# SCH_esp-firework-firing-system-hw1.net
KiCad netlist of a schematic drawn in EasyEDA
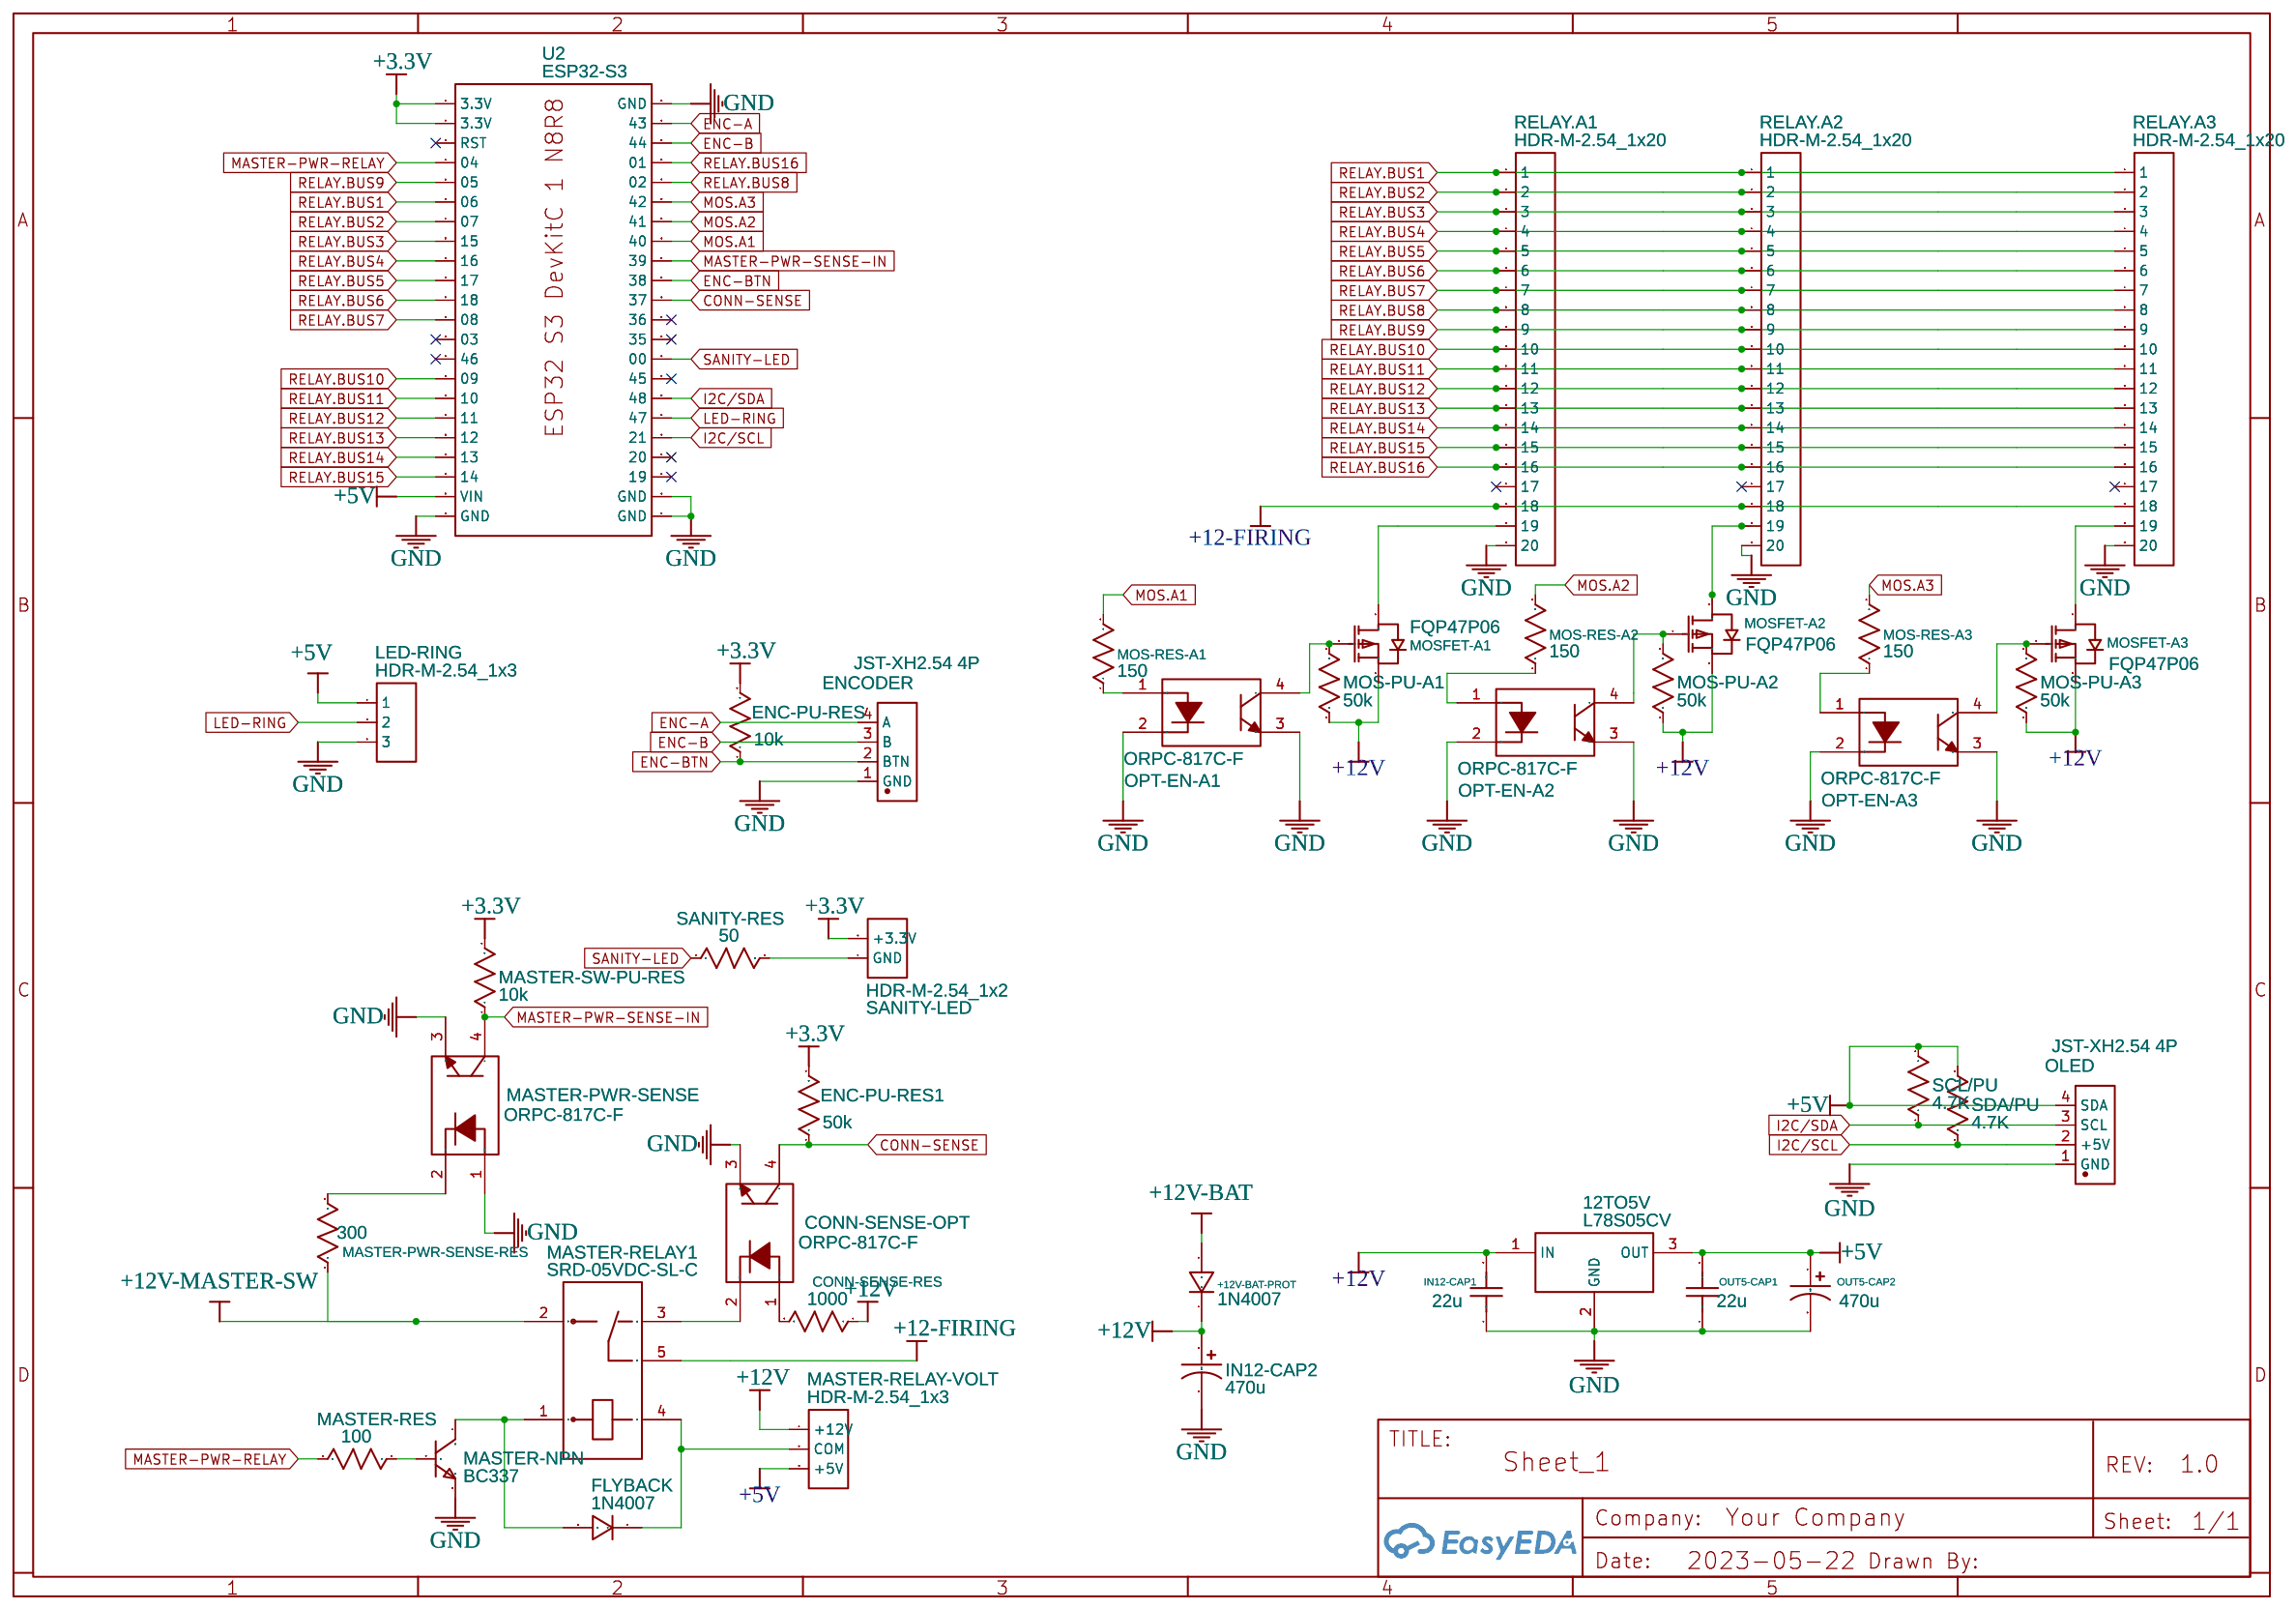
[diagram p0: schematic sheet]

(export (version "E")
  (design (tool "Eeschema 10.0.6"))
  (components
    (comp (ref "+12V-BAT-PROT")
      (value "1N4007")
      (fields (field (name "BOM_Supplier Part") "C106903"))
      (libsource (lib "") (part "1N4007"))
    )
    (comp (ref "12TO5V")
      (value "L78S05CV")
      (fields (field (name "BOM_Supplier Part") "C33043"))
      (libsource (lib "") (part "L78S05CV"))
    )
    (comp (ref "CONN-SENSE-OPT")
      (value "ORPC-817C-F")
      (fields (field (name "BOM_Supplier Part") "C2842770"))
      (libsource (lib "") (part "ORPC-817C-F_2"))
    )
    (comp (ref "CONN-SENSE-RES") (value "1000") (libsource (lib "") (part "R_AXIAL-0.3_US_6")))
    (comp (ref "ENC-PU-RES") (value "10k") (libsource (lib "") (part "R_AXIAL-0.3_US")))
    (comp (ref "ENC-PU-RES1") (value "50k") (libsource (lib "") (part "R_AXIAL-0.3_US")))
    (comp (ref "ENCODER") (value "JST-XH2.54 4P") (libsource (lib "") (part "JST-XH2.54 4P_1")))
    (comp (ref "FLYBACK")
      (value "1N4007")
      (fields (field (name "BOM_Supplier Part") "C106903"))
      (libsource (lib "") (part "1N4007_1"))
    )
    (comp (ref "IN12-CAP1") (value "22u") (libsource (lib "") (part "C_RAD-0.1_US")))
    (comp (ref "IN12-CAP2") (value "470u") (libsource (lib "") (part "CE_TH_D6.3×F2.5_US_1")))
    (comp (ref "LED-RING")
      (value "HDR-M-2.54_1x3")
      (fields (field (name "BOM_Supplier Part") "C180248"))
      (libsource (lib "") (part "HDR-M-2.54_1x3_1"))
    )
    (comp (ref "MASTER-NPN") (value "BC337") (libsource (lib "") (part "BC337")))
    (comp (ref "MASTER-PWR-SENSE")
      (value "ORPC-817C-F")
      (fields (field (name "BOM_Supplier Part") "C2842770"))
      (libsource (lib "") (part "ORPC-817C-F"))
    )
    (comp (ref "MASTER-PWR-SENSE-RES") (value "300") (libsource (lib "") (part "R_AXIAL-0.3_US_9")))
    (comp (ref "MASTER-RELAY-VOLT")
      (value "HDR-M-2.54_1x3")
      (fields (field (name "BOM_Supplier Part") "C180248"))
      (libsource (lib "") (part "HDR-M-2.54_1x3"))
    )
    (comp (ref "MASTER-RELAY1")
      (value "SRD-05VDC-SL-C")
      (fields (field (name "BOM_Supplier Part") "C35449"))
      (libsource (lib "") (part "SRD-05VDC-SL-C"))
    )
    (comp (ref "MASTER-RES") (value "100") (libsource (lib "") (part "R_AXIAL-0.3_US_4")))
    (comp (ref "MASTER-SW-PU-RES") (value "10k") (libsource (lib "") (part "R_AXIAL-0.3_US_8")))
    (comp (ref "MOS-PU-A1") (value "50k") (libsource (lib "") (part "R_AXIAL-0.3_US_3")))
    (comp (ref "MOS-PU-A2") (value "50k") (libsource (lib "") (part "R_AXIAL-0.3_US_3")))
    (comp (ref "MOS-PU-A3") (value "50k") (libsource (lib "") (part "R_AXIAL-0.3_US_3")))
    (comp (ref "MOS-RES-A1") (value "150") (libsource (lib "") (part "R_AXIAL-0.3_US_2")))
    (comp (ref "MOS-RES-A2") (value "150") (libsource (lib "") (part "R_AXIAL-0.3_US_2")))
    (comp (ref "MOS-RES-A3") (value "150") (libsource (lib "") (part "R_AXIAL-0.3_US_2")))
    (comp (ref "MOSFET-A1")
      (value "FQP47P06")
      (fields (field (name "BOM_Supplier Part") "C462765"))
      (libsource (lib "") (part "FQP47P06"))
    )
    (comp (ref "MOSFET-A2")
      (value "FQP47P06")
      (fields (field (name "BOM_Supplier Part") "C462765"))
      (libsource (lib "") (part "FQP47P06"))
    )
    (comp (ref "MOSFET-A3")
      (value "FQP47P06")
      (fields (field (name "BOM_Supplier Part") "C462765"))
      (libsource (lib "") (part "FQP47P06"))
    )
    (comp (ref "OLED") (value "JST-XH2.54 4P") (libsource (lib "") (part "JST-XH2.54 4P")))
    (comp (ref "OPT-EN-A1")
      (value "ORPC-817C-F")
      (fields (field (name "BOM_Supplier Part") "C2842770"))
      (libsource (lib "") (part "ORPC-817C-F_1"))
    )
    (comp (ref "OPT-EN-A2")
      (value "ORPC-817C-F")
      (fields (field (name "BOM_Supplier Part") "C2842770"))
      (libsource (lib "") (part "ORPC-817C-F_1"))
    )
    (comp (ref "OPT-EN-A3")
      (value "ORPC-817C-F")
      (fields (field (name "BOM_Supplier Part") "C2842770"))
      (libsource (lib "") (part "ORPC-817C-F_1"))
    )
    (comp (ref "OUT5-CAP1") (value "22u") (libsource (lib "") (part "C_RAD-0.1_US_1")))
    (comp (ref "OUT5-CAP2") (value "470u") (libsource (lib "") (part "CE_TH_D6.3×F2.5_US")))
    (comp (ref "RELAY.A1")
      (value "HDR-M-2.54_1x20")
      (fields (field (name "BOM_Supplier Part") "C50981"))
      (libsource (lib "") (part "HDR-M-2.54_1x20"))
    )
    (comp (ref "RELAY.A2")
      (value "HDR-M-2.54_1x20")
      (fields (field (name "BOM_Supplier Part") "C50981"))
      (libsource (lib "") (part "HDR-M-2.54_1x20"))
    )
    (comp (ref "RELAY.A3")
      (value "HDR-M-2.54_1x20")
      (fields (field (name "BOM_Supplier Part") "C50981"))
      (libsource (lib "") (part "HDR-M-2.54_1x20"))
    )
    (comp (ref "SANITY-LED")
      (value "HDR-M-2.54_1x2")
      (fields (field (name "BOM_Supplier Part") "C124375"))
      (libsource (lib "") (part "HDR-M-2.54_1x2"))
    )
    (comp (ref "SANITY-RES") (value "50") (libsource (lib "") (part "R_AXIAL-0.3_US_7")))
    (comp (ref "SCL/PU") (value "4.7K") (libsource (lib "") (part "R_AXIAL-0.3_US_1")))
    (comp (ref "SDA/PU") (value "4.7K") (libsource (lib "") (part "R_AXIAL-0.3_US_5")))
    (comp (ref "U2") (value "ESP32-S3") (libsource (lib "") (part "ESP32-S3")))
  )
  (nets
    (net (code "1") (name "+3.3V") (class "Default")
      (node (ref "ENC-PU-RES") (pin "2") (pinfunction "2_2") (pintype "unspecified"))
      (node (ref "ENC-PU-RES1") (pin "2") (pinfunction "2_2") (pintype "unspecified"))
      (node (ref "MASTER-SW-PU-RES") (pin "2") (pinfunction "2_2") (pintype "unspecified"))
      (node (ref "SANITY-LED") (pin "2") (pinfunction "+3.3V_2") (pintype "unspecified"))
      (node (ref "U2") (pin "1") (pinfunction "3.3V_1") (pintype "unspecified"))
      (node (ref "U2") (pin "2") (pinfunction "3.3V_2") (pintype "unspecified"))
    )
    (net (code "2") (name "+5V") (class "Default")
      (node (ref "12TO5V") (pin "3") (pinfunction "OUT_3") (pintype "passive"))
      (node (ref "LED-RING") (pin "1") (pinfunction "1_1") (pintype "input"))
      (node (ref "MASTER-RELAY-VOLT") (pin "3") (pinfunction "+5V_3") (pintype "input"))
      (node (ref "OLED") (pin "4") (pinfunction "SDA_4") (pintype "unspecified"))
      (node (ref "OUT5-CAP1") (pin "2") (pinfunction "2_2") (pintype "unspecified"))
      (node (ref "OUT5-CAP2") (pin "1") (pinfunction "1_1") (pintype "unspecified"))
      (node (ref "SCL/PU") (pin "2") (pinfunction "2_2") (pintype "unspecified"))
      (node (ref "SDA/PU") (pin "2") (pinfunction "2_2") (pintype "unspecified"))
      (node (ref "U2") (pin "21") (pinfunction "VIN_21") (pintype "unspecified"))
    )
    (net (code "3") (name "+12-FIRING") (class "Default")
      (node (ref "MASTER-RELAY1") (pin "5") (pinfunction "5_5") (pintype "input"))
      (node (ref "RELAY.A1") (pin "18") (pinfunction "18_18") (pintype "unspecified"))
      (node (ref "RELAY.A2") (pin "18") (pinfunction "18_18") (pintype "unspecified"))
      (node (ref "RELAY.A3") (pin "18") (pinfunction "18_18") (pintype "unspecified"))
    )
    (net (code "4") (name "+12V") (class "Default")
      (node (ref "+12V-BAT-PROT") (pin "1") (pinfunction "1_1") (pintype "unspecified"))
      (node (ref "12TO5V") (pin "1") (pinfunction "IN_1") (pintype "passive"))
      (node (ref "CONN-SENSE-RES") (pin "1") (pinfunction "1_1") (pintype "unspecified"))
      (node (ref "IN12-CAP1") (pin "2") (pinfunction "2_2") (pintype "unspecified"))
      (node (ref "IN12-CAP2") (pin "1") (pinfunction "1_1") (pintype "unspecified"))
      (node (ref "MASTER-RELAY-VOLT") (pin "1") (pinfunction "+12V_1") (pintype "input"))
      (node (ref "MOS-PU-A1") (pin "1") (pinfunction "1_1") (pintype "unspecified"))
      (node (ref "MOS-PU-A2") (pin "1") (pinfunction "1_1") (pintype "unspecified"))
      (node (ref "MOS-PU-A3") (pin "1") (pinfunction "1_1") (pintype "unspecified"))
      (node (ref "MOSFET-A1") (pin "3") (pinfunction "S_3") (pintype "unspecified"))
      (node (ref "MOSFET-A2") (pin "3") (pinfunction "S_3") (pintype "unspecified"))
      (node (ref "MOSFET-A3") (pin "3") (pinfunction "S_3") (pintype "unspecified"))
    )
    (net (code "5") (name "+12V-BAT") (class "Default")
      (node (ref "+12V-BAT-PROT") (pin "2") (pinfunction "2_2") (pintype "unspecified"))
    )
    (net (code "6") (name "+12V-MASTER-SW") (class "Default")
      (node (ref "MASTER-PWR-SENSE-RES") (pin "1") (pinfunction "1_1") (pintype "unspecified"))
      (node (ref "MASTER-RELAY1") (pin "2") (pinfunction "2_2") (pintype "input"))
    )
    (net (code "7") (name "CONN-SENSE") (class "Default")
      (node (ref "CONN-SENSE-OPT") (pin "4") (pinfunction "4_4") (pintype "unspecified"))
      (node (ref "ENC-PU-RES1") (pin "1") (pinfunction "1_1") (pintype "unspecified"))
      (node (ref "U2") (pin "33") (pinfunction "37_33") (pintype "unspecified"))
    )
    (net (code "8") (name "ENC-A") (class "Default")
      (node (ref "ENCODER") (pin "4") (pinfunction "A_4") (pintype "unspecified"))
      (node (ref "U2") (pin "24") (pinfunction "43_24") (pintype "unspecified"))
    )
    (net (code "9") (name "ENC-B") (class "Default")
      (node (ref "ENCODER") (pin "3") (pinfunction "B_3") (pintype "unspecified"))
      (node (ref "U2") (pin "25") (pinfunction "44_25") (pintype "unspecified"))
    )
    (net (code "10") (name "ENC-BTN") (class "Default")
      (node (ref "ENC-PU-RES") (pin "1") (pinfunction "1_1") (pintype "unspecified"))
      (node (ref "ENCODER") (pin "2") (pinfunction "BTN_2") (pintype "unspecified"))
      (node (ref "U2") (pin "32") (pinfunction "38_32") (pintype "unspecified"))
    )
    (net (code "11") (name "GND") (class "Default")
      (node (ref "12TO5V") (pin "2") (pinfunction "GND_2") (pintype "passive"))
      (node (ref "CONN-SENSE-OPT") (pin "3") (pinfunction "3_3") (pintype "unspecified"))
      (node (ref "ENCODER") (pin "1") (pinfunction "GND_1") (pintype "unspecified"))
      (node (ref "IN12-CAP1") (pin "1") (pinfunction "1_1") (pintype "unspecified"))
      (node (ref "IN12-CAP2") (pin "2") (pinfunction "2_2") (pintype "unspecified"))
      (node (ref "LED-RING") (pin "3") (pinfunction "3_3") (pintype "input"))
      (node (ref "MASTER-NPN") (pin "3") (pinfunction "E_3") (pintype "unspecified"))
      (node (ref "MASTER-PWR-SENSE") (pin "1") (pinfunction "1_1") (pintype "unspecified"))
      (node (ref "MASTER-PWR-SENSE") (pin "3") (pinfunction "3_3") (pintype "unspecified"))
      (node (ref "OLED") (pin "1") (pinfunction "GND_1") (pintype "unspecified"))
      (node (ref "OPT-EN-A1") (pin "2") (pinfunction "2_2") (pintype "unspecified"))
      (node (ref "OPT-EN-A1") (pin "3") (pinfunction "3_3") (pintype "unspecified"))
      (node (ref "OPT-EN-A2") (pin "2") (pinfunction "2_2") (pintype "unspecified"))
      (node (ref "OPT-EN-A2") (pin "3") (pinfunction "3_3") (pintype "unspecified"))
      (node (ref "OPT-EN-A3") (pin "2") (pinfunction "2_2") (pintype "unspecified"))
      (node (ref "OPT-EN-A3") (pin "3") (pinfunction "3_3") (pintype "unspecified"))
      (node (ref "OUT5-CAP1") (pin "1") (pinfunction "1_1") (pintype "unspecified"))
      (node (ref "OUT5-CAP2") (pin "2") (pinfunction "2_2") (pintype "unspecified"))
      (node (ref "RELAY.A1") (pin "20") (pinfunction "20_20") (pintype "unspecified"))
      (node (ref "RELAY.A2") (pin "20") (pinfunction "20_20") (pintype "unspecified"))
      (node (ref "RELAY.A3") (pin "20") (pinfunction "20_20") (pintype "unspecified"))
      (node (ref "U2") (pin "22") (pinfunction "GND_22") (pintype "unspecified"))
      (node (ref "U2") (pin "23") (pinfunction "GND_23") (pintype "unspecified"))
      (node (ref "U2") (pin "43") (pinfunction "GND_43") (pintype "unspecified"))
      (node (ref "U2") (pin "44") (pinfunction "GND_44") (pintype "unspecified"))
    )
    (net (code "12") (name "I2C{slash}SCL") (class "Default")
      (node (ref "OLED") (pin "2") (pinfunction "+5V_2") (pintype "unspecified"))
      (node (ref "SDA/PU") (pin "1") (pinfunction "1_1") (pintype "unspecified"))
      (node (ref "U2") (pin "40") (pinfunction "21_40") (pintype "unspecified"))
    )
    (net (code "13") (name "I2C{slash}SDA") (class "Default")
      (node (ref "OLED") (pin "3") (pinfunction "SCL_3") (pintype "unspecified"))
      (node (ref "SCL/PU") (pin "1") (pinfunction "1_1") (pintype "unspecified"))
      (node (ref "U2") (pin "38") (pinfunction "48_38") (pintype "unspecified"))
    )
    (net (code "14") (name "LED-RING") (class "Default")
      (node (ref "LED-RING") (pin "2") (pinfunction "2_2") (pintype "input"))
      (node (ref "U2") (pin "39") (pinfunction "47_39") (pintype "unspecified"))
    )
    (net (code "15") (name "MASTER-PWR-RELAY") (class "Default")
      (node (ref "MASTER-RES") (pin "2") (pinfunction "2_2") (pintype "unspecified"))
      (node (ref "U2") (pin "4") (pinfunction "04_4") (pintype "unspecified"))
    )
    (net (code "16") (name "MASTER-PWR-SENSE-IN") (class "Default")
      (node (ref "MASTER-PWR-SENSE") (pin "4") (pinfunction "4_4") (pintype "unspecified"))
      (node (ref "MASTER-SW-PU-RES") (pin "1") (pinfunction "1_1") (pintype "unspecified"))
      (node (ref "U2") (pin "31") (pinfunction "39_31") (pintype "unspecified"))
    )
    (net (code "17") (name "MOS.A1") (class "Default")
      (node (ref "MOS-RES-A1") (pin "2") (pinfunction "2_2") (pintype "unspecified"))
      (node (ref "U2") (pin "30") (pinfunction "40_30") (pintype "unspecified"))
    )
    (net (code "18") (name "MOS.A2") (class "Default")
      (node (ref "MOS-RES-A2") (pin "2") (pinfunction "2_2") (pintype "unspecified"))
      (node (ref "U2") (pin "29") (pinfunction "41_29") (pintype "unspecified"))
    )
    (net (code "19") (name "MOS.A3") (class "Default")
      (node (ref "MOS-RES-A3") (pin "2") (pinfunction "2_2") (pintype "unspecified"))
      (node (ref "U2") (pin "28") (pinfunction "42_28") (pintype "unspecified"))
    )
    (net (code "20") (name "Net-(CONN-SENSE-OPT-Pad1)") (class "Default")
      (node (ref "CONN-SENSE-OPT") (pin "1") (pinfunction "1_1") (pintype "unspecified"))
      (node (ref "CONN-SENSE-RES") (pin "2") (pinfunction "2_2") (pintype "unspecified"))
    )
    (net (code "21") (name "Net-(CONN-SENSE-OPT-Pad2)") (class "Default")
      (node (ref "CONN-SENSE-OPT") (pin "2") (pinfunction "2_2") (pintype "unspecified"))
      (node (ref "MASTER-RELAY1") (pin "3") (pinfunction "3_3") (pintype "input"))
    )
    (net (code "22") (name "Net-(MASTER-NPN-B)") (class "Default")
      (node (ref "MASTER-NPN") (pin "2") (pinfunction "B_2") (pintype "unspecified"))
      (node (ref "MASTER-RES") (pin "1") (pinfunction "1_1") (pintype "unspecified"))
    )
    (net (code "23") (name "Net-(MASTER-NPN-C)") (class "Default")
      (node (ref "FLYBACK") (pin "2") (pinfunction "2_2") (pintype "unspecified"))
      (node (ref "MASTER-NPN") (pin "1") (pinfunction "C_1") (pintype "unspecified"))
      (node (ref "MASTER-RELAY1") (pin "1") (pinfunction "1_1") (pintype "input"))
    )
    (net (code "24") (name "Net-(MASTER-PWR-SENSE-Pad2)") (class "Default")
      (node (ref "MASTER-PWR-SENSE") (pin "2") (pinfunction "2_2") (pintype "unspecified"))
      (node (ref "MASTER-PWR-SENSE-RES") (pin "2") (pinfunction "2_2") (pintype "unspecified"))
    )
    (net (code "25") (name "Net-(MASTER-RELAY-VOLT-COM)") (class "Default")
      (node (ref "FLYBACK") (pin "1") (pinfunction "1_1") (pintype "unspecified"))
      (node (ref "MASTER-RELAY-VOLT") (pin "2") (pinfunction "COM_2") (pintype "input"))
      (node (ref "MASTER-RELAY1") (pin "4") (pinfunction "4_4") (pintype "input"))
    )
    (net (code "26") (name "Net-(MOS-RES-A1-Pad1)") (class "Default")
      (node (ref "MOS-RES-A1") (pin "1") (pinfunction "1_1") (pintype "unspecified"))
      (node (ref "OPT-EN-A1") (pin "1") (pinfunction "1_1") (pintype "unspecified"))
    )
    (net (code "27") (name "Net-(MOS-RES-A2-Pad1)") (class "Default")
      (node (ref "MOS-RES-A2") (pin "1") (pinfunction "1_1") (pintype "unspecified"))
      (node (ref "OPT-EN-A2") (pin "1") (pinfunction "1_1") (pintype "unspecified"))
    )
    (net (code "28") (name "Net-(MOS-RES-A3-Pad1)") (class "Default")
      (node (ref "MOS-RES-A3") (pin "1") (pinfunction "1_1") (pintype "unspecified"))
      (node (ref "OPT-EN-A3") (pin "1") (pinfunction "1_1") (pintype "unspecified"))
    )
    (net (code "29") (name "Net-(MOSFET-A1-D)") (class "Default")
      (node (ref "MOSFET-A1") (pin "2") (pinfunction "D_2") (pintype "unspecified"))
      (node (ref "RELAY.A1") (pin "19") (pinfunction "19_19") (pintype "unspecified"))
    )
    (net (code "30") (name "Net-(MOSFET-A1-G)") (class "Default")
      (node (ref "MOS-PU-A1") (pin "2") (pinfunction "2_2") (pintype "unspecified"))
      (node (ref "MOSFET-A1") (pin "1") (pinfunction "G_1") (pintype "unspecified"))
      (node (ref "OPT-EN-A1") (pin "4") (pinfunction "4_4") (pintype "unspecified"))
    )
    (net (code "31") (name "Net-(MOSFET-A2-D)") (class "Default")
      (node (ref "MOSFET-A2") (pin "2") (pinfunction "D_2") (pintype "unspecified"))
      (node (ref "RELAY.A2") (pin "19") (pinfunction "19_19") (pintype "unspecified"))
    )
    (net (code "32") (name "Net-(MOSFET-A2-G)") (class "Default")
      (node (ref "MOS-PU-A2") (pin "2") (pinfunction "2_2") (pintype "unspecified"))
      (node (ref "MOSFET-A2") (pin "1") (pinfunction "G_1") (pintype "unspecified"))
      (node (ref "OPT-EN-A2") (pin "4") (pinfunction "4_4") (pintype "unspecified"))
    )
    (net (code "33") (name "Net-(MOSFET-A3-D)") (class "Default")
      (node (ref "MOSFET-A3") (pin "2") (pinfunction "D_2") (pintype "unspecified"))
      (node (ref "RELAY.A3") (pin "19") (pinfunction "19_19") (pintype "unspecified"))
    )
    (net (code "34") (name "Net-(MOSFET-A3-G)") (class "Default")
      (node (ref "MOS-PU-A3") (pin "2") (pinfunction "2_2") (pintype "unspecified"))
      (node (ref "MOSFET-A3") (pin "1") (pinfunction "G_1") (pintype "unspecified"))
      (node (ref "OPT-EN-A3") (pin "4") (pinfunction "4_4") (pintype "unspecified"))
    )
    (net (code "35") (name "Net-(SANITY-LED-GND)") (class "Default")
      (node (ref "SANITY-LED") (pin "1") (pinfunction "GND_1") (pintype "unspecified"))
      (node (ref "SANITY-RES") (pin "2") (pinfunction "2_2") (pintype "unspecified"))
    )
    (net (code "36") (name "RELAY.BUS1") (class "Default")
      (node (ref "RELAY.A1") (pin "1") (pinfunction "1_1") (pintype "unspecified"))
      (node (ref "RELAY.A2") (pin "1") (pinfunction "1_1") (pintype "unspecified"))
      (node (ref "RELAY.A3") (pin "1") (pinfunction "1_1") (pintype "unspecified"))
      (node (ref "U2") (pin "6") (pinfunction "06_6") (pintype "unspecified"))
    )
    (net (code "37") (name "RELAY.BUS2") (class "Default")
      (node (ref "RELAY.A1") (pin "2") (pinfunction "2_2") (pintype "unspecified"))
      (node (ref "RELAY.A2") (pin "2") (pinfunction "2_2") (pintype "unspecified"))
      (node (ref "RELAY.A3") (pin "2") (pinfunction "2_2") (pintype "unspecified"))
      (node (ref "U2") (pin "7") (pinfunction "07_7") (pintype "unspecified"))
    )
    (net (code "38") (name "RELAY.BUS3") (class "Default")
      (node (ref "RELAY.A1") (pin "3") (pinfunction "3_3") (pintype "unspecified"))
      (node (ref "RELAY.A2") (pin "3") (pinfunction "3_3") (pintype "unspecified"))
      (node (ref "RELAY.A3") (pin "3") (pinfunction "3_3") (pintype "unspecified"))
      (node (ref "U2") (pin "8") (pinfunction "15_8") (pintype "unspecified"))
    )
    (net (code "39") (name "RELAY.BUS4") (class "Default")
      (node (ref "RELAY.A1") (pin "4") (pinfunction "4_4") (pintype "unspecified"))
      (node (ref "RELAY.A2") (pin "4") (pinfunction "4_4") (pintype "unspecified"))
      (node (ref "RELAY.A3") (pin "4") (pinfunction "4_4") (pintype "unspecified"))
      (node (ref "U2") (pin "9") (pinfunction "16_9") (pintype "unspecified"))
    )
    (net (code "40") (name "RELAY.BUS5") (class "Default")
      (node (ref "RELAY.A1") (pin "5") (pinfunction "5_5") (pintype "unspecified"))
      (node (ref "RELAY.A2") (pin "5") (pinfunction "5_5") (pintype "unspecified"))
      (node (ref "RELAY.A3") (pin "5") (pinfunction "5_5") (pintype "unspecified"))
      (node (ref "U2") (pin "10") (pinfunction "17_10") (pintype "unspecified"))
    )
    (net (code "41") (name "RELAY.BUS6") (class "Default")
      (node (ref "RELAY.A1") (pin "6") (pinfunction "6_6") (pintype "unspecified"))
      (node (ref "RELAY.A2") (pin "6") (pinfunction "6_6") (pintype "unspecified"))
      (node (ref "RELAY.A3") (pin "6") (pinfunction "6_6") (pintype "unspecified"))
      (node (ref "U2") (pin "11") (pinfunction "18_11") (pintype "unspecified"))
    )
    (net (code "42") (name "RELAY.BUS7") (class "Default")
      (node (ref "RELAY.A1") (pin "7") (pinfunction "7_7") (pintype "unspecified"))
      (node (ref "RELAY.A2") (pin "7") (pinfunction "7_7") (pintype "unspecified"))
      (node (ref "RELAY.A3") (pin "7") (pinfunction "7_7") (pintype "unspecified"))
      (node (ref "U2") (pin "12") (pinfunction "08_12") (pintype "unspecified"))
    )
    (net (code "43") (name "RELAY.BUS8") (class "Default")
      (node (ref "RELAY.A1") (pin "8") (pinfunction "8_8") (pintype "unspecified"))
      (node (ref "RELAY.A2") (pin "8") (pinfunction "8_8") (pintype "unspecified"))
      (node (ref "RELAY.A3") (pin "8") (pinfunction "8_8") (pintype "unspecified"))
      (node (ref "U2") (pin "27") (pinfunction "02_27") (pintype "unspecified"))
    )
    (net (code "44") (name "RELAY.BUS9") (class "Default")
      (node (ref "RELAY.A1") (pin "9") (pinfunction "9_9") (pintype "unspecified"))
      (node (ref "RELAY.A2") (pin "9") (pinfunction "9_9") (pintype "unspecified"))
      (node (ref "RELAY.A3") (pin "9") (pinfunction "9_9") (pintype "unspecified"))
      (node (ref "U2") (pin "5") (pinfunction "05_5") (pintype "unspecified"))
    )
    (net (code "45") (name "RELAY.BUS10") (class "Default")
      (node (ref "RELAY.A1") (pin "10") (pinfunction "10_10") (pintype "unspecified"))
      (node (ref "RELAY.A2") (pin "10") (pinfunction "10_10") (pintype "unspecified"))
      (node (ref "RELAY.A3") (pin "10") (pinfunction "10_10") (pintype "unspecified"))
      (node (ref "U2") (pin "15") (pinfunction "09_15") (pintype "unspecified"))
    )
    (net (code "46") (name "RELAY.BUS11") (class "Default")
      (node (ref "RELAY.A1") (pin "11") (pinfunction "11_11") (pintype "unspecified"))
      (node (ref "RELAY.A2") (pin "11") (pinfunction "11_11") (pintype "unspecified"))
      (node (ref "RELAY.A3") (pin "11") (pinfunction "11_11") (pintype "unspecified"))
      (node (ref "U2") (pin "16") (pinfunction "10_16") (pintype "unspecified"))
    )
    (net (code "47") (name "RELAY.BUS12") (class "Default")
      (node (ref "RELAY.A1") (pin "12") (pinfunction "12_12") (pintype "unspecified"))
      (node (ref "RELAY.A2") (pin "12") (pinfunction "12_12") (pintype "unspecified"))
      (node (ref "RELAY.A3") (pin "12") (pinfunction "12_12") (pintype "unspecified"))
      (node (ref "U2") (pin "17") (pinfunction "11_17") (pintype "unspecified"))
    )
    (net (code "48") (name "RELAY.BUS13") (class "Default")
      (node (ref "RELAY.A1") (pin "13") (pinfunction "13_13") (pintype "unspecified"))
      (node (ref "RELAY.A2") (pin "13") (pinfunction "13_13") (pintype "unspecified"))
      (node (ref "RELAY.A3") (pin "13") (pinfunction "13_13") (pintype "unspecified"))
      (node (ref "U2") (pin "18") (pinfunction "12_18") (pintype "unspecified"))
    )
    (net (code "49") (name "RELAY.BUS14") (class "Default")
      (node (ref "RELAY.A1") (pin "14") (pinfunction "14_14") (pintype "unspecified"))
      (node (ref "RELAY.A2") (pin "14") (pinfunction "14_14") (pintype "unspecified"))
      (node (ref "RELAY.A3") (pin "14") (pinfunction "14_14") (pintype "unspecified"))
      (node (ref "U2") (pin "19") (pinfunction "13_19") (pintype "unspecified"))
    )
    (net (code "50") (name "RELAY.BUS15") (class "Default")
      (node (ref "RELAY.A1") (pin "15") (pinfunction "15_15") (pintype "unspecified"))
      (node (ref "RELAY.A2") (pin "15") (pinfunction "15_15") (pintype "unspecified"))
      (node (ref "RELAY.A3") (pin "15") (pinfunction "15_15") (pintype "unspecified"))
      (node (ref "U2") (pin "20") (pinfunction "14_20") (pintype "unspecified"))
    )
    (net (code "51") (name "RELAY.BUS16") (class "Default")
      (node (ref "RELAY.A1") (pin "16") (pinfunction "16_16") (pintype "unspecified"))
      (node (ref "RELAY.A2") (pin "16") (pinfunction "16_16") (pintype "unspecified"))
      (node (ref "RELAY.A3") (pin "16") (pinfunction "16_16") (pintype "unspecified"))
      (node (ref "U2") (pin "26") (pinfunction "01_26") (pintype "unspecified"))
    )
    (net (code "52") (name "SANITY-LED") (class "Default")
      (node (ref "SANITY-RES") (pin "1") (pinfunction "1_1") (pintype "unspecified"))
      (node (ref "U2") (pin "36") (pinfunction "00_36") (pintype "unspecified"))
    )
    (net (code "53") (name "unconnected-(RELAY.A1-Pad17)") (class "Default")
      (node (ref "RELAY.A1") (pin "17") (pinfunction "17_17") (pintype "unspecified+no_connect"))
    )
    (net (code "54") (name "unconnected-(RELAY.A2-Pad17)") (class "Default")
      (node (ref "RELAY.A2") (pin "17") (pinfunction "17_17") (pintype "unspecified+no_connect"))
    )
    (net (code "55") (name "unconnected-(RELAY.A3-Pad17)") (class "Default")
      (node (ref "RELAY.A3") (pin "17") (pinfunction "17_17") (pintype "unspecified+no_connect"))
    )
    (net (code "56") (name "unconnected-(U2-03-Pad13)") (class "Default")
      (node (ref "U2") (pin "13") (pinfunction "03_13") (pintype "unspecified+no_connect"))
    )
    (net (code "57") (name "unconnected-(U2-19-Pad42)") (class "Default")
      (node (ref "U2") (pin "42") (pinfunction "19_42") (pintype "unspecified+no_connect"))
    )
    (net (code "58") (name "unconnected-(U2-20-Pad41)") (class "Default")
      (node (ref "U2") (pin "41") (pinfunction "20_41") (pintype "unspecified+no_connect"))
    )
    (net (code "59") (name "unconnected-(U2-36-Pad34)") (class "Default")
      (node (ref "U2") (pin "34") (pinfunction "36_34") (pintype "unspecified+no_connect"))
    )
    (net (code "60") (name "unconnected-(U2-45-Pad37)") (class "Default")
      (node (ref "U2") (pin "37") (pinfunction "45_37") (pintype "unspecified+no_connect"))
    )
    (net (code "61") (name "unconnected-(U2-46-Pad14)") (class "Default")
      (node (ref "U2") (pin "14") (pinfunction "46_14") (pintype "unspecified+no_connect"))
    )
    (net (code "62") (name "unconnected-(U2-Pad35)") (class "Default")
      (node (ref "U2") (pin "35") (pinfunction "35_35") (pintype "unspecified+no_connect"))
    )
    (net (code "63") (name "unconnected-(U2-RST-Pad3)") (class "Default")
      (node (ref "U2") (pin "3") (pinfunction "RST_3") (pintype "unspecified+no_connect"))
    )
  )
)
